# 02-bluetooth-V2_4.net
KiCad netlist of a schematic drawn in Altium Designer
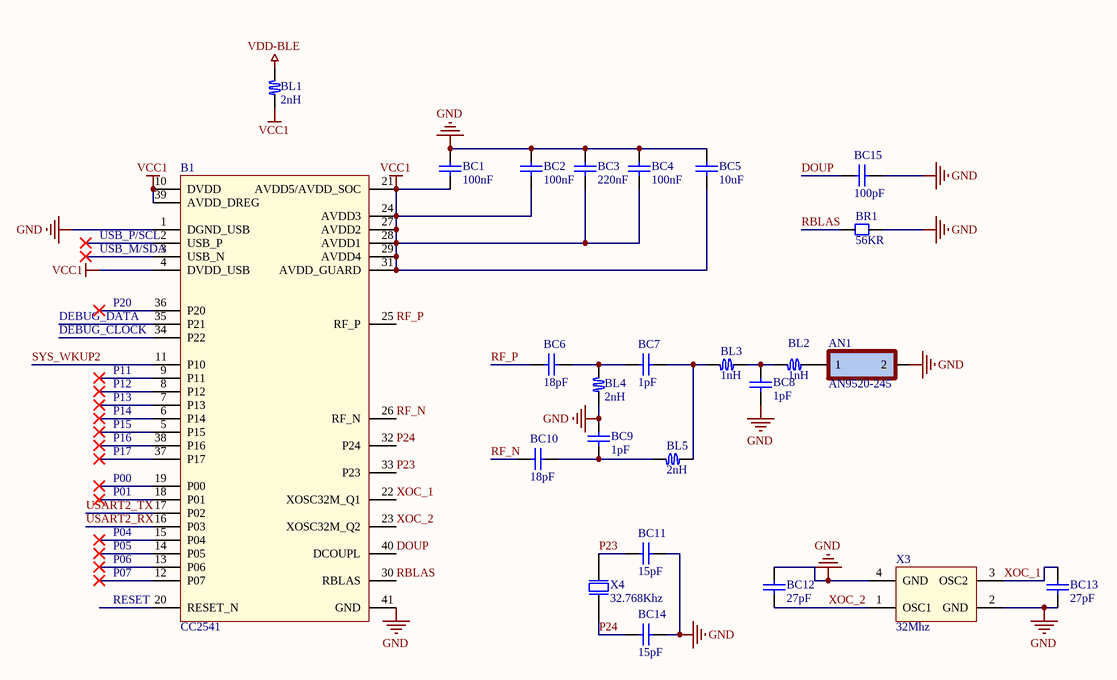
[diagram p0: 02-bluetooth-V2.4.SchDoc]

(export (version "E")
  (design (tool "Eeschema 10.0.6"))
  (components
    (comp (ref "AN1")
      (value "AN9520-245")
      (footprint "AN-5120")
      (description "2.4G全向天线 蓝牙天线 陶瓷贴片 WIFI内置")
      (libsource (lib "tianxiaohua_Schlib") (part "AN9520-245"))
    )
    (comp (ref "B1")
      (value "CC2541")
      (footprint "QFN40-CC254X")
      (description "低功耗蓝牙芯片")
      (libsource (lib "tianxiaohua_Schlib") (part "CC2541"))
    )
    (comp (ref "BC1")
      (value "100nF")
      (footprint "CC1005-0402")
      (description "贴片电容")
      (libsource (lib "tianxiaohua_Schlib") (part "Chip capacitor"))
    )
    (comp (ref "BC2")
      (value "100nF")
      (footprint "CC1005-0402")
      (description "贴片电容")
      (libsource (lib "tianxiaohua_Schlib") (part "Chip capacitor"))
    )
    (comp (ref "BC3")
      (value "220nF")
      (footprint "CC1005-0402")
      (description "贴片电容")
      (libsource (lib "tianxiaohua_Schlib") (part "Chip capacitor"))
    )
    (comp (ref "BC4")
      (value "100nF")
      (footprint "CC1005-0402")
      (description "贴片电容")
      (libsource (lib "tianxiaohua_Schlib") (part "Chip capacitor"))
    )
    (comp (ref "BC5")
      (value "10uF")
      (footprint "CC1005-0402")
      (description "贴片电容")
      (libsource (lib "tianxiaohua_Schlib") (part "Chip capacitor"))
    )
    (comp (ref "BC6")
      (value "18pF")
      (footprint "CC1005-0402")
      (description "贴片电容")
      (libsource (lib "tianxiaohua_Schlib") (part "Chip capacitor"))
    )
    (comp (ref "BC7")
      (value "1pF")
      (footprint "CC1005-0402")
      (description "贴片电容")
      (libsource (lib "tianxiaohua_Schlib") (part "Chip capacitor"))
    )
    (comp (ref "BC8")
      (value "1pF")
      (footprint "CC1005-0402")
      (description "贴片电容")
      (libsource (lib "tianxiaohua_Schlib") (part "Chip capacitor"))
    )
    (comp (ref "BC9")
      (value "1pF")
      (footprint "CC1005-0402")
      (description "贴片电容")
      (libsource (lib "tianxiaohua_Schlib") (part "Chip capacitor"))
    )
    (comp (ref "BC10")
      (value "18pF")
      (footprint "CC1005-0402")
      (description "贴片电容")
      (libsource (lib "tianxiaohua_Schlib") (part "Chip capacitor"))
    )
    (comp (ref "BC11")
      (value "15pF")
      (footprint "CC1005-0402")
      (description "贴片电容")
      (libsource (lib "tianxiaohua_Schlib") (part "Chip capacitor"))
    )
    (comp (ref "BC12")
      (value "27pF")
      (footprint "CC1005-0402")
      (description "贴片电容")
      (libsource (lib "tianxiaohua_Schlib") (part "Chip capacitor"))
    )
    (comp (ref "BC13")
      (value "27pF")
      (footprint "CC1005-0402")
      (description "贴片电容")
      (libsource (lib "tianxiaohua_Schlib") (part "Chip capacitor"))
    )
    (comp (ref "BC14")
      (value "15pF")
      (footprint "CC1005-0402")
      (description "贴片电容")
      (libsource (lib "tianxiaohua_Schlib") (part "Chip capacitor"))
    )
    (comp (ref "BC15")
      (value "100pF")
      (footprint "CC1005-0402")
      (description "贴片电容")
      (libsource (lib "tianxiaohua_Schlib") (part "Chip capacitor"))
    )
    (comp (ref "BL1")
      (value "2nH")
      (footprint "Inductor-0402")
      (description "0402封装的电感")
      (libsource (lib "tianxiaohua_Schlib") (part "Inductor-0402"))
    )
    (comp (ref "BL2")
      (value "1nH")
      (footprint "Inductor-0402")
      (description "0402封装的电感")
      (libsource (lib "") (part "Inductor-0402_1"))
    )
    (comp (ref "BL3")
      (value "1nH")
      (footprint "Inductor-0402")
      (description "0402封装的电感")
      (libsource (lib "") (part "Inductor-0402_1"))
    )
    (comp (ref "BL4")
      (value "2nH")
      (footprint "Inductor-0402")
      (description "0402封装的电感")
      (libsource (lib "tianxiaohua_Schlib") (part "Inductor-0402"))
    )
    (comp (ref "BL5")
      (value "2nH")
      (footprint "Inductor-0402")
      (description "0402封装的电感")
      (libsource (lib "") (part "Inductor-0402_1"))
    )
    (comp (ref "BR1")
      (value "56KR")
      (footprint "CR1005-0402")
      (description "贴片电阻")
      (libsource (lib "tianxiaohua_Schlib") (part "Chip resistor"))
    )
    (comp (ref "X3")
      (value "32Mhz")
      (footprint "XTAL-2016")
      (description "2016封装的晶振")
      (libsource (lib "tianxiaohua_Schlib") (part "XTAL 2016"))
    )
    (comp (ref "X4")
      (value "32.768Khz")
      (footprint "XTAL-2012")
      (description "2012封装的时钟晶振")
      (libsource (lib "tianxiaohua_Schlib") (part "XTAL 2012"))
    )
  )
  (nets
    (net (code "1") (name "/DEBUG_CLOCK") (class "Default")
      (node (ref "B1") (pin "34") (pinfunction "P22_34") (pintype "passive"))
    )
    (net (code "2") (name "/DEBUG_DATA") (class "Default")
      (node (ref "B1") (pin "35") (pinfunction "P21_35") (pintype "passive"))
    )
    (net (code "3") (name "/DOUP") (class "Default")
      (node (ref "B1") (pin "40") (pinfunction "DCOUPL_40") (pintype "passive"))
      (node (ref "BC15") (pin "2") (pinfunction "2_2") (pintype "passive"))
    )
    (net (code "4") (name "/P00") (class "Default")
      (node (ref "B1") (pin "19") (pinfunction "P00_19") (pintype "passive+no_connect"))
    )
    (net (code "5") (name "/P01") (class "Default")
      (node (ref "B1") (pin "18") (pinfunction "P01_18") (pintype "passive+no_connect"))
    )
    (net (code "6") (name "/P04") (class "Default")
      (node (ref "B1") (pin "15") (pinfunction "P04_15") (pintype "passive+no_connect"))
    )
    (net (code "7") (name "/P05") (class "Default")
      (node (ref "B1") (pin "14") (pinfunction "P05_14") (pintype "passive+no_connect"))
    )
    (net (code "8") (name "/P06") (class "Default")
      (node (ref "B1") (pin "13") (pinfunction "P06_13") (pintype "passive+no_connect"))
    )
    (net (code "9") (name "/P07") (class "Default")
      (node (ref "B1") (pin "12") (pinfunction "P07_12") (pintype "passive+no_connect"))
    )
    (net (code "10") (name "/P11") (class "Default")
      (node (ref "B1") (pin "9") (pinfunction "P11_9") (pintype "passive+no_connect"))
    )
    (net (code "11") (name "/P12") (class "Default")
      (node (ref "B1") (pin "8") (pinfunction "P12_8") (pintype "passive+no_connect"))
    )
    (net (code "12") (name "/P13") (class "Default")
      (node (ref "B1") (pin "7") (pinfunction "P13_7") (pintype "passive+no_connect"))
    )
    (net (code "13") (name "/P14") (class "Default")
      (node (ref "B1") (pin "6") (pinfunction "P14_6") (pintype "passive+no_connect"))
    )
    (net (code "14") (name "/P15") (class "Default")
      (node (ref "B1") (pin "5") (pinfunction "P15_5") (pintype "passive+no_connect"))
    )
    (net (code "15") (name "/P16") (class "Default")
      (node (ref "B1") (pin "38") (pinfunction "P16_38") (pintype "passive+no_connect"))
    )
    (net (code "16") (name "/P17") (class "Default")
      (node (ref "B1") (pin "37") (pinfunction "P17_37") (pintype "passive+no_connect"))
    )
    (net (code "17") (name "/P20") (class "Default")
      (node (ref "B1") (pin "36") (pinfunction "P20_36") (pintype "passive+no_connect"))
    )
    (net (code "18") (name "/P23") (class "Default")
      (node (ref "B1") (pin "33") (pinfunction "P23_33") (pintype "passive"))
      (node (ref "BC11") (pin "1") (pinfunction "1_1") (pintype "passive"))
      (node (ref "X4") (pin "2") (pinfunction "2_2") (pintype "passive"))
    )
    (net (code "19") (name "/P24") (class "Default")
      (node (ref "B1") (pin "32") (pinfunction "P24_32") (pintype "passive"))
      (node (ref "BC14") (pin "1") (pinfunction "1_1") (pintype "passive"))
      (node (ref "X4") (pin "1") (pinfunction "1_1") (pintype "passive"))
    )
    (net (code "20") (name "/RBLAS") (class "Default")
      (node (ref "B1") (pin "30") (pinfunction "RBLAS_30") (pintype "passive"))
      (node (ref "BR1") (pin "1") (pinfunction "1_1") (pintype "passive"))
    )
    (net (code "21") (name "/RESET") (class "Default")
      (node (ref "B1") (pin "20") (pinfunction "RESET_N_20") (pintype "passive"))
    )
    (net (code "22") (name "/RF_N") (class "Default")
      (node (ref "B1") (pin "26") (pinfunction "RF_N_26") (pintype "passive"))
      (node (ref "BC10") (pin "2") (pinfunction "2_2") (pintype "passive"))
    )
    (net (code "23") (name "/RF_P") (class "Default")
      (node (ref "B1") (pin "25") (pinfunction "RF_P_25") (pintype "passive"))
      (node (ref "BC6") (pin "2") (pinfunction "2_2") (pintype "passive"))
    )
    (net (code "24") (name "/SYS_WKUP2") (class "Default")
      (node (ref "B1") (pin "11") (pinfunction "P10_11") (pintype "passive"))
    )
    (net (code "25") (name "/USART2_RX") (class "Default")
      (node (ref "B1") (pin "16") (pinfunction "P03_16") (pintype "passive"))
    )
    (net (code "26") (name "/USART2_TX") (class "Default")
      (node (ref "B1") (pin "17") (pinfunction "P02_17") (pintype "passive"))
    )
    (net (code "27") (name "/USB_M{slash}SDA") (class "Default")
      (node (ref "B1") (pin "3") (pinfunction "USB_N_3") (pintype "passive+no_connect"))
    )
    (net (code "28") (name "/USB_P{slash}SCL") (class "Default")
      (node (ref "B1") (pin "2") (pinfunction "USB_P_2") (pintype "passive+no_connect"))
    )
    (net (code "29") (name "/XOC_1") (class "Default")
      (node (ref "B1") (pin "22") (pinfunction "XOSC32M_Q1_22") (pintype "passive"))
      (node (ref "BC13") (pin "2") (pinfunction "2_2") (pintype "passive"))
      (node (ref "X3") (pin "3") (pinfunction "OSC2_3") (pintype "passive"))
    )
    (net (code "30") (name "/XOC_2") (class "Default")
      (node (ref "B1") (pin "23") (pinfunction "XOSC32M_Q2_23") (pintype "passive"))
      (node (ref "BC12") (pin "1") (pinfunction "1_1") (pintype "passive"))
      (node (ref "X3") (pin "1") (pinfunction "OSC1_1") (pintype "passive"))
    )
    (net (code "31") (name "GND") (class "Default")
      (node (ref "AN1") (pin "2") (pinfunction "2_2") (pintype "passive"))
      (node (ref "B1") (pin "1") (pinfunction "DGND_USB_1") (pintype "passive"))
      (node (ref "B1") (pin "41") (pinfunction "GND_41") (pintype "passive"))
      (node (ref "BC1") (pin "2") (pinfunction "2_2") (pintype "passive"))
      (node (ref "BC11") (pin "2") (pinfunction "2_2") (pintype "passive"))
      (node (ref "BC12") (pin "2") (pinfunction "2_2") (pintype "passive"))
      (node (ref "BC13") (pin "1") (pinfunction "1_1") (pintype "passive"))
      (node (ref "BC14") (pin "2") (pinfunction "2_2") (pintype "passive"))
      (node (ref "BC15") (pin "1") (pinfunction "1_1") (pintype "passive"))
      (node (ref "BC2") (pin "2") (pinfunction "2_2") (pintype "passive"))
      (node (ref "BC3") (pin "2") (pinfunction "2_2") (pintype "passive"))
      (node (ref "BC4") (pin "2") (pinfunction "2_2") (pintype "passive"))
      (node (ref "BC5") (pin "2") (pinfunction "2_2") (pintype "passive"))
      (node (ref "BC8") (pin "1") (pinfunction "1_1") (pintype "passive"))
      (node (ref "BC9") (pin "1") (pinfunction "1_1") (pintype "passive"))
      (node (ref "BL4") (pin "1") (pinfunction "1_1") (pintype "passive"))
      (node (ref "BR1") (pin "2") (pinfunction "2_2") (pintype "passive"))
      (node (ref "X3") (pin "2") (pinfunction "GND_2") (pintype "passive"))
      (node (ref "X3") (pin "4") (pinfunction "GND_4") (pintype "passive"))
    )
    (net (code "32") (name "Net-(AN1-Pad1)") (class "Default")
      (node (ref "AN1") (pin "1") (pinfunction "1_1") (pintype "passive"))
      (node (ref "BL2") (pin "1") (pinfunction "1_1") (pintype "passive"))
    )
    (net (code "33") (name "Net-(BC6-Pad1)") (class "Default")
      (node (ref "BC6") (pin "1") (pinfunction "1_1") (pintype "passive"))
      (node (ref "BC7") (pin "1") (pinfunction "1_1") (pintype "passive"))
      (node (ref "BL4") (pin "2") (pinfunction "2_2") (pintype "passive"))
    )
    (net (code "34") (name "Net-(BC7-Pad2)") (class "Default")
      (node (ref "BC7") (pin "2") (pinfunction "2_2") (pintype "passive"))
      (node (ref "BL3") (pin "2") (pinfunction "2_2") (pintype "passive"))
      (node (ref "BL5") (pin "1") (pinfunction "1_1") (pintype "passive"))
    )
    (net (code "35") (name "Net-(BC8-Pad2)") (class "Default")
      (node (ref "BC8") (pin "2") (pinfunction "2_2") (pintype "passive"))
      (node (ref "BL2") (pin "2") (pinfunction "2_2") (pintype "passive"))
      (node (ref "BL3") (pin "1") (pinfunction "1_1") (pintype "passive"))
    )
    (net (code "36") (name "Net-(BC10-Pad1)") (class "Default")
      (node (ref "BC10") (pin "1") (pinfunction "1_1") (pintype "passive"))
      (node (ref "BC9") (pin "2") (pinfunction "2_2") (pintype "passive"))
      (node (ref "BL5") (pin "2") (pinfunction "2_2") (pintype "passive"))
    )
    (net (code "37") (name "VCC1") (class "Default")
      (node (ref "B1") (pin "10") (pinfunction "DVDD_10") (pintype "passive"))
      (node (ref "B1") (pin "21") (pinfunction "AVDD5/AVDD_SOC_21") (pintype "passive"))
      (node (ref "B1") (pin "24") (pinfunction "AVDD3_24") (pintype "passive"))
      (node (ref "B1") (pin "27") (pinfunction "AVDD2_27") (pintype "passive"))
      (node (ref "B1") (pin "28") (pinfunction "AVDD1_28") (pintype "passive"))
      (node (ref "B1") (pin "29") (pinfunction "AVDD4_29") (pintype "passive"))
      (node (ref "B1") (pin "31") (pinfunction "AVDD_GUARD_31") (pintype "passive"))
      (node (ref "B1") (pin "39") (pinfunction "AVDD_DREG_39") (pintype "passive"))
      (node (ref "B1") (pin "4") (pinfunction "DVDD_USB_4") (pintype "passive"))
      (node (ref "BC1") (pin "1") (pinfunction "1_1") (pintype "passive"))
      (node (ref "BC2") (pin "1") (pinfunction "1_1") (pintype "passive"))
      (node (ref "BC3") (pin "1") (pinfunction "1_1") (pintype "passive"))
      (node (ref "BC4") (pin "1") (pinfunction "1_1") (pintype "passive"))
      (node (ref "BC5") (pin "1") (pinfunction "1_1") (pintype "passive"))
      (node (ref "BL1") (pin "1") (pinfunction "1_1") (pintype "passive"))
    )
    (net (code "38") (name "VDD-BLE") (class "Default")
      (node (ref "BL1") (pin "2") (pinfunction "2_2") (pintype "passive"))
    )
  )
)
